# switch.net
KiCad netlist of a schematic drawn in EAGLE
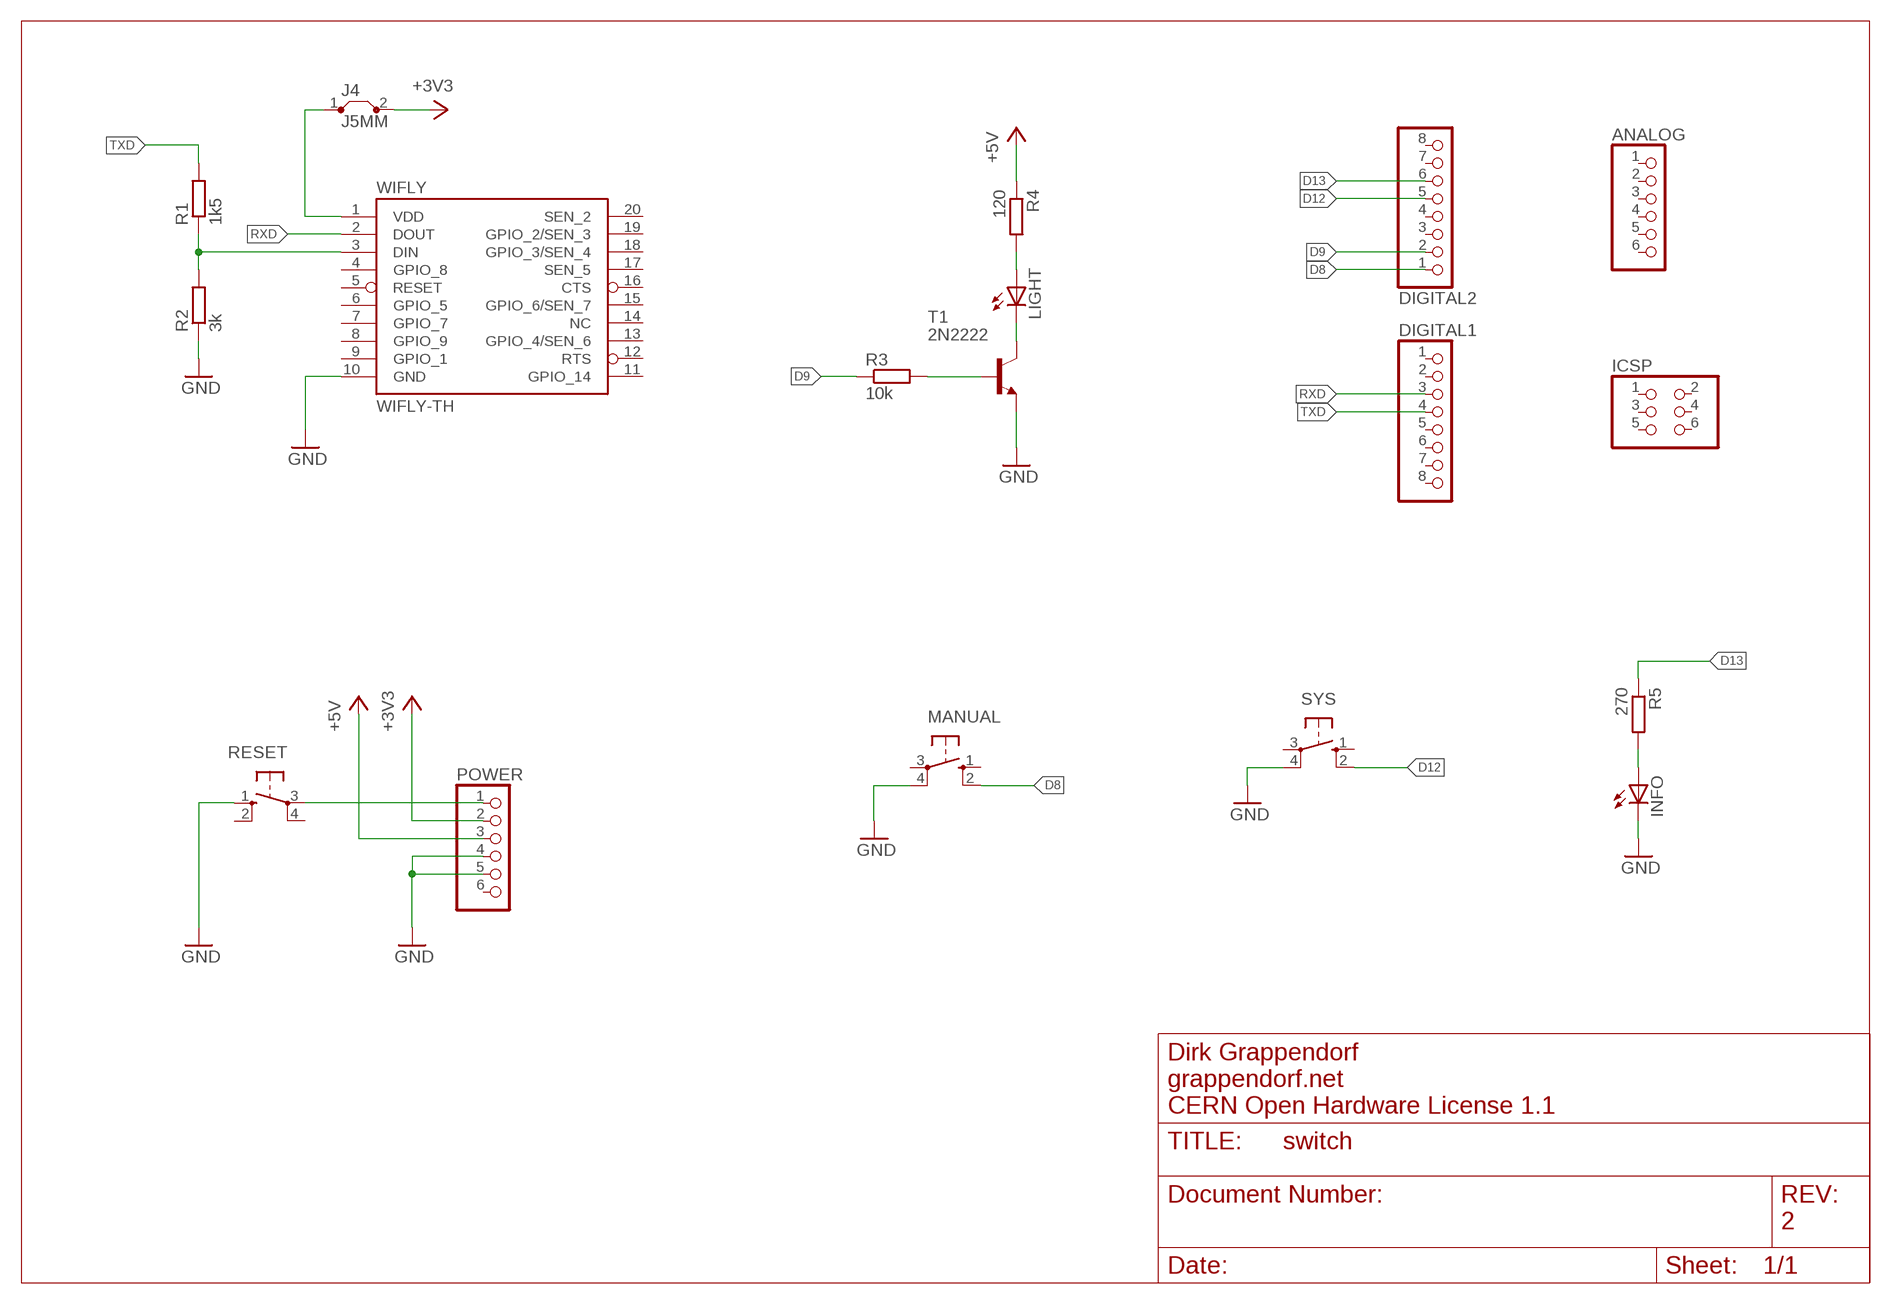
[diagram p0: schematic, sheet 1]

(export (version "E")
  (design (tool "Eeschema 10.0.6"))
  (components
    (comp (ref "ANALOG")
      (value "PINHD-1X6")
      (footprint "eagle-import:1X06")
      (libsource (lib "eagle-import") (part "PINHD-1X6"))
    )
    (comp (ref "DIGITAL1")
      (value "PINHD-1X8TH")
      (footprint "eagle-import:1X08-TH")
      (libsource (lib "eagle-import") (part "PINHD-1X8TH"))
    )
    (comp (ref "DIGITAL2")
      (value "PINHD-1X8_2.54")
      (footprint "eagle-import:1X08")
      (libsource (lib "eagle-import") (part "PINHD-1X8_2.54"))
    )
    (comp (ref "ICSP")
      (value "PINHD-2X3")
      (footprint "eagle-import:2X03")
      (libsource (lib "eagle-import") (part "PINHD-2X3"))
    )
    (comp (ref "INFO")
      (value "LED3MM")
      (footprint "eagle-import:LED3MM")
      (libsource (lib "eagle-import") (part "LED3MM"))
    )
    (comp (ref "J4")
      (value "J5MM")
      (footprint "eagle-import:05")
      (libsource (lib "eagle-import") (part "J5MM"))
    )
    (comp (ref "LIGHT")
      (value "LED5MM")
      (footprint "eagle-import:LED5MM")
      (libsource (lib "eagle-import") (part "LED5MM"))
    )
    (comp (ref "MANUAL")
      (value "10-XX")
      (footprint "eagle-import:B3F-10XX")
      (libsource (lib "eagle-import") (part "10-XX"))
    )
    (comp (ref "POWER")
      (value "PINHD-1X6_2.54")
      (footprint "eagle-import:1X06")
      (libsource (lib "eagle-import") (part "PINHD-1X6_2.54"))
    )
    (comp (ref "R1")
      (value "1k5")
      (footprint "eagle-import:0204_7")
      (libsource (lib "eagle-import") (part "R-EU_0204/7"))
    )
    (comp (ref "R2")
      (value "3k")
      (footprint "eagle-import:0204_7")
      (libsource (lib "eagle-import") (part "R-EU_0204/7"))
    )
    (comp (ref "R3")
      (value "10k")
      (footprint "eagle-import:0204_7")
      (libsource (lib "eagle-import") (part "R-EU_0204/7"))
    )
    (comp (ref "R4")
      (value "120")
      (footprint "eagle-import:0204_7")
      (libsource (lib "eagle-import") (part "R-EU_0204/7"))
    )
    (comp (ref "R5")
      (value "270")
      (footprint "eagle-import:0204_7")
      (libsource (lib "eagle-import") (part "R-EU_0204/7"))
    )
    (comp (ref "RESET")
      (value "10-XX")
      (footprint "eagle-import:B3F-10XX")
      (libsource (lib "eagle-import") (part "10-XX"))
    )
    (comp (ref "SYS")
      (value "10-XX")
      (footprint "eagle-import:B3F-10XX")
      (libsource (lib "eagle-import") (part "10-XX"))
    )
    (comp (ref "T1")
      (value "2N2222")
      (footprint "eagle-import:TO18")
      (libsource (lib "eagle-import") (part "2N2222"))
    )
    (comp (ref "WIFLY")
      (value "WIFLY-TH")
      (footprint "eagle-import:WIFLY-TH")
      (libsource (lib "eagle-import") (part "WIFLY-TH"))
    )
  )
  (nets
    (net (code "1") (name "+3V3") (class "Default")
      (node (ref "J4") (pin "2") (pinfunction "2_2") (pintype "passive"))
      (node (ref "POWER") (pin "2") (pinfunction "2_2") (pintype "passive"))
    )
    (net (code "2") (name "+5V") (class "Default")
      (node (ref "POWER") (pin "3") (pinfunction "3_3") (pintype "passive"))
      (node (ref "R4") (pin "1") (pinfunction "1_1") (pintype "passive"))
    )
    (net (code "3") (name "D8") (class "Default")
      (node (ref "DIGITAL2") (pin "1") (pinfunction "1_1") (pintype "passive"))
      (node (ref "MANUAL") (pin "2") (pinfunction "S1_2") (pintype "passive"))
    )
    (net (code "4") (name "D9") (class "Default")
      (node (ref "DIGITAL2") (pin "2") (pinfunction "2_2") (pintype "passive"))
      (node (ref "R3") (pin "1") (pinfunction "1_1") (pintype "passive"))
    )
    (net (code "5") (name "D12") (class "Default")
      (node (ref "DIGITAL2") (pin "5") (pinfunction "5_5") (pintype "passive"))
      (node (ref "SYS") (pin "2") (pinfunction "S1_2") (pintype "passive"))
    )
    (net (code "6") (name "D13") (class "Default")
      (node (ref "DIGITAL2") (pin "6") (pinfunction "6_6") (pintype "passive"))
      (node (ref "R5") (pin "1") (pinfunction "1_1") (pintype "passive"))
    )
    (net (code "7") (name "GND") (class "Default")
      (node (ref "INFO") (pin "K") (pinfunction "C_K") (pintype "passive"))
      (node (ref "MANUAL") (pin "4") (pinfunction "P1_4") (pintype "passive"))
      (node (ref "POWER") (pin "4") (pinfunction "4_4") (pintype "passive"))
      (node (ref "POWER") (pin "5") (pinfunction "5_5") (pintype "passive"))
      (node (ref "R2") (pin "1") (pinfunction "1_1") (pintype "passive"))
      (node (ref "RESET") (pin "1") (pinfunction "S_1") (pintype "passive"))
      (node (ref "SYS") (pin "4") (pinfunction "P1_4") (pintype "passive"))
      (node (ref "T1") (pin "1") (pinfunction "E_1") (pintype "passive"))
      (node (ref "WIFLY") (pin "10") (pinfunction "GND_10") (pintype "power_in"))
    )
    (net (code "8") (name "Net-(INFO-PadA)") (class "Default")
      (node (ref "INFO") (pin "A") (pinfunction "A_A") (pintype "passive"))
      (node (ref "R5") (pin "2") (pinfunction "2_2") (pintype "passive"))
    )
    (net (code "9") (name "Net-(LIGHT-C)") (class "Default")
      (node (ref "LIGHT") (pin "K") (pinfunction "C_K") (pintype "passive"))
      (node (ref "T1") (pin "3") (pinfunction "C_3") (pintype "passive"))
    )
    (net (code "10") (name "Net-(LIGHT-PadA)") (class "Default")
      (node (ref "LIGHT") (pin "A") (pinfunction "A_A") (pintype "passive"))
      (node (ref "R4") (pin "2") (pinfunction "2_2") (pintype "passive"))
    )
    (net (code "11") (name "Net-(RESET-P)") (class "Default")
      (node (ref "POWER") (pin "1") (pinfunction "1_1") (pintype "passive"))
      (node (ref "RESET") (pin "3") (pinfunction "P_3") (pintype "passive"))
    )
    (net (code "12") (name "Net-(T1-B)") (class "Default")
      (node (ref "R3") (pin "2") (pinfunction "2_2") (pintype "passive"))
      (node (ref "T1") (pin "2") (pinfunction "B_2") (pintype "passive"))
    )
    (net (code "13") (name "Net-(WIFLY-DIN)") (class "Default")
      (node (ref "R1") (pin "1") (pinfunction "1_1") (pintype "passive"))
      (node (ref "R2") (pin "2") (pinfunction "2_2") (pintype "passive"))
      (node (ref "WIFLY") (pin "3") (pinfunction "DIN_3") (pintype "input"))
    )
    (net (code "14") (name "Net-(WIFLY-VDD)") (class "Default")
      (node (ref "J4") (pin "1") (pinfunction "1_1") (pintype "passive"))
      (node (ref "WIFLY") (pin "1") (pinfunction "VDD_1") (pintype "power_in"))
    )
    (net (code "15") (name "RXD") (class "Default")
      (node (ref "DIGITAL1") (pin "3") (pinfunction "3_3") (pintype "passive"))
      (node (ref "WIFLY") (pin "2") (pinfunction "DOUT_2") (pintype "output"))
    )
    (net (code "16") (name "TXD") (class "Default")
      (node (ref "DIGITAL1") (pin "4") (pinfunction "4_4") (pintype "passive"))
      (node (ref "R1") (pin "2") (pinfunction "2_2") (pintype "passive"))
    )
    (net (code "17") (name "unconnected-(ANALOG-Pad1)") (class "Default")
      (node (ref "ANALOG") (pin "1") (pinfunction "1_1") (pintype "passive"))
    )
    (net (code "18") (name "unconnected-(ANALOG-Pad2)") (class "Default")
      (node (ref "ANALOG") (pin "2") (pinfunction "2_2") (pintype "passive"))
    )
    (net (code "19") (name "unconnected-(ANALOG-Pad3)") (class "Default")
      (node (ref "ANALOG") (pin "3") (pinfunction "3_3") (pintype "passive"))
    )
    (net (code "20") (name "unconnected-(ANALOG-Pad4)") (class "Default")
      (node (ref "ANALOG") (pin "4") (pinfunction "4_4") (pintype "passive"))
    )
    (net (code "21") (name "unconnected-(ANALOG-Pad5)") (class "Default")
      (node (ref "ANALOG") (pin "5") (pinfunction "5_5") (pintype "passive"))
    )
    (net (code "22") (name "unconnected-(ANALOG-Pad6)") (class "Default")
      (node (ref "ANALOG") (pin "6") (pinfunction "6_6") (pintype "passive"))
    )
    (net (code "23") (name "unconnected-(DIGITAL1-Pad1)") (class "Default")
      (node (ref "DIGITAL1") (pin "1") (pinfunction "1_1") (pintype "passive"))
    )
    (net (code "24") (name "unconnected-(DIGITAL1-Pad2)") (class "Default")
      (node (ref "DIGITAL1") (pin "2") (pinfunction "2_2") (pintype "passive"))
    )
    (net (code "25") (name "unconnected-(DIGITAL1-Pad5)") (class "Default")
      (node (ref "DIGITAL1") (pin "5") (pinfunction "5_5") (pintype "passive"))
    )
    (net (code "26") (name "unconnected-(DIGITAL1-Pad6)") (class "Default")
      (node (ref "DIGITAL1") (pin "6") (pinfunction "6_6") (pintype "passive"))
    )
    (net (code "27") (name "unconnected-(DIGITAL1-Pad7)") (class "Default")
      (node (ref "DIGITAL1") (pin "7") (pinfunction "7_7") (pintype "passive"))
    )
    (net (code "28") (name "unconnected-(DIGITAL1-Pad8)") (class "Default")
      (node (ref "DIGITAL1") (pin "8") (pinfunction "8_8") (pintype "passive"))
    )
    (net (code "29") (name "unconnected-(DIGITAL2-Pad3)") (class "Default")
      (node (ref "DIGITAL2") (pin "3") (pinfunction "3_3") (pintype "passive"))
    )
    (net (code "30") (name "unconnected-(DIGITAL2-Pad4)") (class "Default")
      (node (ref "DIGITAL2") (pin "4") (pinfunction "4_4") (pintype "passive"))
    )
    (net (code "31") (name "unconnected-(DIGITAL2-Pad7)") (class "Default")
      (node (ref "DIGITAL2") (pin "7") (pinfunction "7_7") (pintype "passive"))
    )
    (net (code "32") (name "unconnected-(DIGITAL2-Pad8)") (class "Default")
      (node (ref "DIGITAL2") (pin "8") (pinfunction "8_8") (pintype "passive"))
    )
    (net (code "33") (name "unconnected-(ICSP-Pad1)") (class "Default")
      (node (ref "ICSP") (pin "1") (pinfunction "1_1") (pintype "passive"))
    )
    (net (code "34") (name "unconnected-(ICSP-Pad2)") (class "Default")
      (node (ref "ICSP") (pin "2") (pinfunction "2_2") (pintype "passive"))
    )
    (net (code "35") (name "unconnected-(ICSP-Pad3)") (class "Default")
      (node (ref "ICSP") (pin "3") (pinfunction "3_3") (pintype "passive"))
    )
    (net (code "36") (name "unconnected-(ICSP-Pad4)") (class "Default")
      (node (ref "ICSP") (pin "4") (pinfunction "4_4") (pintype "passive"))
    )
    (net (code "37") (name "unconnected-(ICSP-Pad5)") (class "Default")
      (node (ref "ICSP") (pin "5") (pinfunction "5_5") (pintype "passive"))
    )
    (net (code "38") (name "unconnected-(ICSP-Pad6)") (class "Default")
      (node (ref "ICSP") (pin "6") (pinfunction "6_6") (pintype "passive"))
    )
    (net (code "39") (name "unconnected-(MANUAL-P-Pad3)") (class "Default")
      (node (ref "MANUAL") (pin "3") (pinfunction "P_3") (pintype "passive"))
    )
    (net (code "40") (name "unconnected-(MANUAL-S-Pad1)") (class "Default")
      (node (ref "MANUAL") (pin "1") (pinfunction "S_1") (pintype "passive"))
    )
    (net (code "41") (name "unconnected-(POWER-Pad6)") (class "Default")
      (node (ref "POWER") (pin "6") (pinfunction "6_6") (pintype "passive"))
    )
    (net (code "42") (name "unconnected-(RESET-P1-Pad4)") (class "Default")
      (node (ref "RESET") (pin "4") (pinfunction "P1_4") (pintype "passive"))
    )
    (net (code "43") (name "unconnected-(RESET-S1-Pad2)") (class "Default")
      (node (ref "RESET") (pin "2") (pinfunction "S1_2") (pintype "passive"))
    )
    (net (code "44") (name "unconnected-(SYS-P-Pad3)") (class "Default")
      (node (ref "SYS") (pin "3") (pinfunction "P_3") (pintype "passive"))
    )
    (net (code "45") (name "unconnected-(SYS-S-Pad1)") (class "Default")
      (node (ref "SYS") (pin "1") (pinfunction "S_1") (pintype "passive"))
    )
    (net (code "46") (name "unconnected-(WIFLY-CTS-Pad16)") (class "Default")
      (node (ref "WIFLY") (pin "16") (pinfunction "CTS_16") (pintype "input"))
    )
    (net (code "47") (name "unconnected-(WIFLY-GPIO_1-Pad9)") (class "Default")
      (node (ref "WIFLY") (pin "9") (pinfunction "GPIO_1_9") (pintype "bidirectional"))
    )
    (net (code "48") (name "unconnected-(WIFLY-GPIO_2{slash}SEN_3-Pad19)") (class "Default")
      (node (ref "WIFLY") (pin "19") (pinfunction "GPIO_2/SEN_3_19") (pintype "bidirectional"))
    )
    (net (code "49") (name "unconnected-(WIFLY-GPIO_3{slash}SEN_4-Pad18)") (class "Default")
      (node (ref "WIFLY") (pin "18") (pinfunction "GPIO_3/SEN_4_18") (pintype "bidirectional"))
    )
    (net (code "50") (name "unconnected-(WIFLY-GPIO_4{slash}SEN_6-Pad13)") (class "Default")
      (node (ref "WIFLY") (pin "13") (pinfunction "GPIO_4/SEN_6_13") (pintype "bidirectional"))
    )
    (net (code "51") (name "unconnected-(WIFLY-GPIO_5-Pad6)") (class "Default")
      (node (ref "WIFLY") (pin "6") (pinfunction "GPIO_5_6") (pintype "bidirectional"))
    )
    (net (code "52") (name "unconnected-(WIFLY-GPIO_6{slash}SEN_7-Pad15)") (class "Default")
      (node (ref "WIFLY") (pin "15") (pinfunction "GPIO_6/SEN_7_15") (pintype "bidirectional"))
    )
    (net (code "53") (name "unconnected-(WIFLY-GPIO_7-Pad7)") (class "Default")
      (node (ref "WIFLY") (pin "7") (pinfunction "GPIO_7_7") (pintype "bidirectional"))
    )
    (net (code "54") (name "unconnected-(WIFLY-GPIO_8-Pad4)") (class "Default")
      (node (ref "WIFLY") (pin "4") (pinfunction "GPIO_8_4") (pintype "bidirectional"))
    )
    (net (code "55") (name "unconnected-(WIFLY-GPIO_9-Pad8)") (class "Default")
      (node (ref "WIFLY") (pin "8") (pinfunction "GPIO_9_8") (pintype "bidirectional"))
    )
    (net (code "56") (name "unconnected-(WIFLY-GPIO_14-Pad11)") (class "Default")
      (node (ref "WIFLY") (pin "11") (pinfunction "GPIO_14_11") (pintype "bidirectional"))
    )
    (net (code "57") (name "unconnected-(WIFLY-NC-Pad14)") (class "Default")
      (node (ref "WIFLY") (pin "14") (pinfunction "NC_14") (pintype "bidirectional"))
    )
    (net (code "58") (name "unconnected-(WIFLY-RESET-Pad5)") (class "Default")
      (node (ref "WIFLY") (pin "5") (pinfunction "RESET_5") (pintype "input"))
    )
    (net (code "59") (name "unconnected-(WIFLY-RTS-Pad12)") (class "Default")
      (node (ref "WIFLY") (pin "12") (pinfunction "RTS_12") (pintype "output"))
    )
    (net (code "60") (name "unconnected-(WIFLY-SEN_2-Pad20)") (class "Default")
      (node (ref "WIFLY") (pin "20") (pinfunction "SEN_2_20") (pintype "bidirectional"))
    )
    (net (code "61") (name "unconnected-(WIFLY-SEN_5-Pad17)") (class "Default")
      (node (ref "WIFLY") (pin "17") (pinfunction "SEN_5_17") (pintype "bidirectional"))
    )
  )
)
